# power_module.net
KiCad netlist of a schematic drawn in Altium Designer
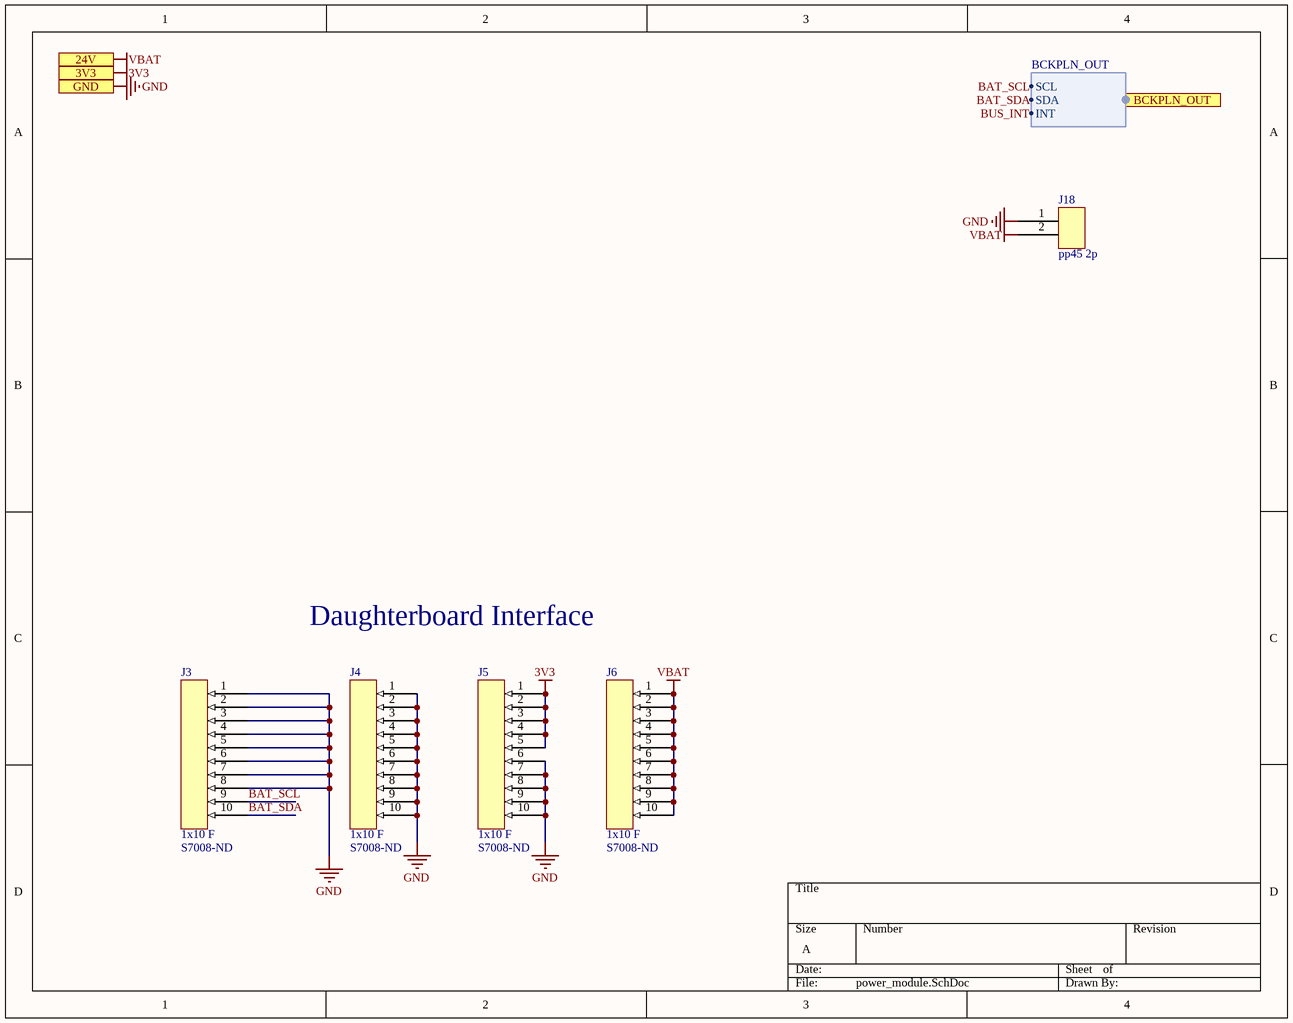
[diagram p0: power_module.SchDoc]

(export (version "E")
  (design (tool "Eeschema 10.0.6"))
  (components
    (comp (ref "J3")
      (value "1x10 F")
      (footprint "CONN HDR 1x10 F")
      (description "CONN header 1x10 F")
      (fields (field (name "SUPPLIER PART NUMBER 1") "S7008-ND"))
      (libsource (lib "streetbot") (part "CONN header 1x10 F"))
    )
    (comp (ref "J4")
      (value "1x10 F")
      (footprint "CONN HDR 1x10 F")
      (description "CONN header 1x10 F")
      (fields (field (name "SUPPLIER PART NUMBER 1") "S7008-ND"))
      (libsource (lib "streetbot") (part "CONN header 1x10 F"))
    )
    (comp (ref "J5")
      (value "1x10 F")
      (footprint "CONN HDR 1x10 F")
      (description "CONN header 1x10 F")
      (fields (field (name "SUPPLIER PART NUMBER 1") "S7008-ND"))
      (libsource (lib "streetbot") (part "CONN header 1x10 F"))
    )
    (comp (ref "J6")
      (value "1x10 F")
      (footprint "CONN HDR 1x10 F")
      (description "CONN header 1x10 F")
      (fields (field (name "SUPPLIER PART NUMBER 1") "S7008-ND"))
      (libsource (lib "streetbot") (part "CONN header 1x10 F"))
    )
    (comp (ref "J18")
      (value "pp45 2p")
      (footprint "CONN PP45 2P VERT")
      (description "Heavy Duty Power Connectors PCB45 VERT.MT.SHORT TAIL LP CONT")
      (libsource (lib "streetbot") (part "CONN pp45 1x2 vert"))
    )
  )
  (nets
    (net (code "2") (name "/BAT_SCL") (class "Default") (node (ref "J3") (pin "9") (pintype "input")))
    (net (code "3") (name "/BAT_SDA") (class "Default") (node (ref "J3") (pin "10") (pintype "input")))
    (net (code "6") (name "3V3") (class "Default")
      (node (ref "J5") (pin "1") (pintype "input"))
      (node (ref "J5") (pin "2") (pintype "input"))
      (node (ref "J5") (pin "3") (pintype "input"))
      (node (ref "J5") (pin "4") (pintype "input"))
      (node (ref "J5") (pin "5") (pintype "input"))
    )
    (net (code "7") (name "GND") (class "Default")
      (node (ref "J18") (pin "1") (pintype "passive"))
      (node (ref "J3") (pin "1") (pintype "input"))
      (node (ref "J3") (pin "2") (pintype "input"))
      (node (ref "J3") (pin "3") (pintype "input"))
      (node (ref "J3") (pin "4") (pintype "input"))
      (node (ref "J3") (pin "5") (pintype "input"))
      (node (ref "J3") (pin "6") (pintype "input"))
      (node (ref "J3") (pin "7") (pintype "input"))
      (node (ref "J3") (pin "8") (pintype "input"))
      (node (ref "J4") (pin "1") (pintype "input"))
      (node (ref "J4") (pin "10") (pintype "input"))
      (node (ref "J4") (pin "2") (pintype "input"))
      (node (ref "J4") (pin "3") (pintype "input"))
      (node (ref "J4") (pin "4") (pintype "input"))
      (node (ref "J4") (pin "5") (pintype "input"))
      (node (ref "J4") (pin "6") (pintype "input"))
      (node (ref "J4") (pin "7") (pintype "input"))
      (node (ref "J4") (pin "8") (pintype "input"))
      (node (ref "J4") (pin "9") (pintype "input"))
      (node (ref "J5") (pin "10") (pintype "input"))
      (node (ref "J5") (pin "6") (pintype "input"))
      (node (ref "J5") (pin "7") (pintype "input"))
      (node (ref "J5") (pin "8") (pintype "input"))
      (node (ref "J5") (pin "9") (pintype "input"))
    )
    (net (code "8") (name "VBAT") (class "Default")
      (node (ref "J18") (pin "2") (pintype "passive"))
      (node (ref "J6") (pin "1") (pintype "input"))
      (node (ref "J6") (pin "10") (pintype "input"))
      (node (ref "J6") (pin "2") (pintype "input"))
      (node (ref "J6") (pin "3") (pintype "input"))
      (node (ref "J6") (pin "4") (pintype "input"))
      (node (ref "J6") (pin "5") (pintype "input"))
      (node (ref "J6") (pin "6") (pintype "input"))
      (node (ref "J6") (pin "7") (pintype "input"))
      (node (ref "J6") (pin "8") (pintype "input"))
      (node (ref "J6") (pin "9") (pintype "input"))
    )
  )
)
